# AT28C256_zif.net
KiCad netlist of a schematic drawn in EAGLE
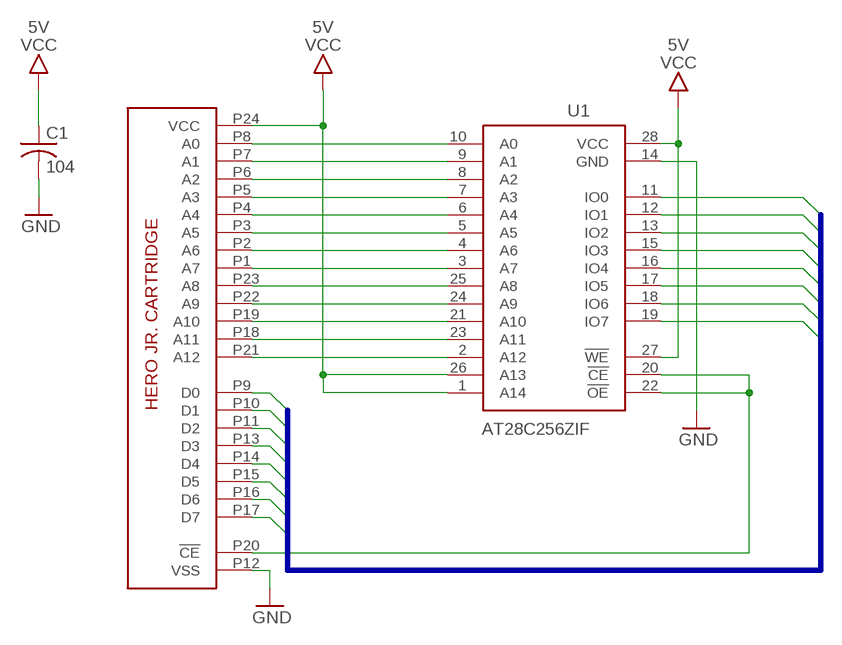
[diagram p0: schematic, sheet 1]

(export (version "E")
  (design (tool "Eeschema 10.0.6"))
  (components
    (comp (ref "C1")
      (value "104")
      (footprint "eagle-import:C050-025X075")
      (libsource (lib "eagle-import") (part "C-US050-025X075"))
    )
    (comp (ref "U$1")
      (value "HEROJRCART")
      (footprint "eagle-import:HEROJRCART")
      (libsource (lib "eagle-import") (part "HEROJRCART"))
    )
    (comp (ref "U1")
      (value "AT28C256ZIF")
      (footprint "eagle-import:DIL28-ZIF")
      (libsource (lib "eagle-import") (part "AT28C256ZIF"))
    )
  )
  (nets
    (net (code "1") (name "/D0") (class "Default")
      (node (ref "U$1") (pin "P9") (pinfunction "D0_P9") (pintype "bidirectional"))
      (node (ref "U1") (pin "11") (pinfunction "IO0_11") (pintype "bidirectional"))
    )
    (net (code "2") (name "/D1") (class "Default")
      (node (ref "U$1") (pin "P10") (pinfunction "D1_P10") (pintype "bidirectional"))
      (node (ref "U1") (pin "12") (pinfunction "IO1_12") (pintype "bidirectional"))
    )
    (net (code "3") (name "/D2") (class "Default")
      (node (ref "U$1") (pin "P11") (pinfunction "D2_P11") (pintype "bidirectional"))
      (node (ref "U1") (pin "13") (pinfunction "IO2_13") (pintype "bidirectional"))
    )
    (net (code "4") (name "/D3") (class "Default")
      (node (ref "U$1") (pin "P13") (pinfunction "D3_P13") (pintype "bidirectional"))
      (node (ref "U1") (pin "15") (pinfunction "IO3_15") (pintype "bidirectional"))
    )
    (net (code "5") (name "/D4") (class "Default")
      (node (ref "U$1") (pin "P14") (pinfunction "D4_P14") (pintype "bidirectional"))
      (node (ref "U1") (pin "16") (pinfunction "IO4_16") (pintype "bidirectional"))
    )
    (net (code "6") (name "/D5") (class "Default")
      (node (ref "U$1") (pin "P15") (pinfunction "D5_P15") (pintype "bidirectional"))
      (node (ref "U1") (pin "17") (pinfunction "IO5_17") (pintype "bidirectional"))
    )
    (net (code "7") (name "/D6") (class "Default")
      (node (ref "U$1") (pin "P16") (pinfunction "D6_P16") (pintype "bidirectional"))
      (node (ref "U1") (pin "18") (pinfunction "IO6_18") (pintype "bidirectional"))
    )
    (net (code "8") (name "/D7") (class "Default")
      (node (ref "U$1") (pin "P17") (pinfunction "D7_P17") (pintype "bidirectional"))
      (node (ref "U1") (pin "19") (pinfunction "IO7_19") (pintype "bidirectional"))
    )
    (net (code "9") (name "5V") (class "Default")
      (node (ref "C1") (pin "1") (pinfunction "1_1") (pintype "passive"))
      (node (ref "U$1") (pin "P24") (pinfunction "VCC_P24") (pintype "bidirectional"))
      (node (ref "U1") (pin "1") (pinfunction "A14_1") (pintype "bidirectional"))
      (node (ref "U1") (pin "26") (pinfunction "A13_26") (pintype "bidirectional"))
      (node (ref "U1") (pin "27") (pinfunction "~{WE}_27") (pintype "bidirectional"))
      (node (ref "U1") (pin "28") (pinfunction "VCC_28") (pintype "bidirectional"))
    )
    (net (code "10") (name "GND") (class "Default")
      (node (ref "C1") (pin "2") (pinfunction "2_2") (pintype "passive"))
      (node (ref "U$1") (pin "P12") (pinfunction "VSS_P12") (pintype "bidirectional"))
      (node (ref "U1") (pin "14") (pinfunction "GND_14") (pintype "bidirectional"))
    )
    (net (code "11") (name "Net-(U$1-A0)") (class "Default")
      (node (ref "U$1") (pin "P8") (pinfunction "A0_P8") (pintype "bidirectional"))
      (node (ref "U1") (pin "10") (pinfunction "A0_10") (pintype "bidirectional"))
    )
    (net (code "12") (name "Net-(U$1-A1)") (class "Default")
      (node (ref "U$1") (pin "P7") (pinfunction "A1_P7") (pintype "bidirectional"))
      (node (ref "U1") (pin "9") (pinfunction "A1_9") (pintype "bidirectional"))
    )
    (net (code "13") (name "Net-(U$1-A2)") (class "Default")
      (node (ref "U$1") (pin "P6") (pinfunction "A2_P6") (pintype "bidirectional"))
      (node (ref "U1") (pin "8") (pinfunction "A2_8") (pintype "bidirectional"))
    )
    (net (code "14") (name "Net-(U$1-A3)") (class "Default")
      (node (ref "U$1") (pin "P5") (pinfunction "A3_P5") (pintype "bidirectional"))
      (node (ref "U1") (pin "7") (pinfunction "A3_7") (pintype "bidirectional"))
    )
    (net (code "15") (name "Net-(U$1-A4)") (class "Default")
      (node (ref "U$1") (pin "P4") (pinfunction "A4_P4") (pintype "bidirectional"))
      (node (ref "U1") (pin "6") (pinfunction "A4_6") (pintype "bidirectional"))
    )
    (net (code "16") (name "Net-(U$1-A5)") (class "Default")
      (node (ref "U$1") (pin "P3") (pinfunction "A5_P3") (pintype "bidirectional"))
      (node (ref "U1") (pin "5") (pinfunction "A5_5") (pintype "bidirectional"))
    )
    (net (code "17") (name "Net-(U$1-A6)") (class "Default")
      (node (ref "U$1") (pin "P2") (pinfunction "A6_P2") (pintype "bidirectional"))
      (node (ref "U1") (pin "4") (pinfunction "A6_4") (pintype "bidirectional"))
    )
    (net (code "18") (name "Net-(U$1-A7)") (class "Default")
      (node (ref "U$1") (pin "P1") (pinfunction "A7_P1") (pintype "bidirectional"))
      (node (ref "U1") (pin "3") (pinfunction "A7_3") (pintype "bidirectional"))
    )
    (net (code "19") (name "Net-(U$1-A8)") (class "Default")
      (node (ref "U$1") (pin "P23") (pinfunction "A8_P23") (pintype "bidirectional"))
      (node (ref "U1") (pin "25") (pinfunction "A8_25") (pintype "bidirectional"))
    )
    (net (code "20") (name "Net-(U$1-A9)") (class "Default")
      (node (ref "U$1") (pin "P22") (pinfunction "A9_P22") (pintype "bidirectional"))
      (node (ref "U1") (pin "24") (pinfunction "A9_24") (pintype "bidirectional"))
    )
    (net (code "21") (name "Net-(U$1-A10)") (class "Default")
      (node (ref "U$1") (pin "P19") (pinfunction "A10_P19") (pintype "bidirectional"))
      (node (ref "U1") (pin "21") (pinfunction "A10_21") (pintype "bidirectional"))
    )
    (net (code "22") (name "Net-(U$1-A11)") (class "Default")
      (node (ref "U$1") (pin "P18") (pinfunction "A11_P18") (pintype "bidirectional"))
      (node (ref "U1") (pin "23") (pinfunction "A11_23") (pintype "bidirectional"))
    )
    (net (code "23") (name "Net-(U$1-A12)") (class "Default")
      (node (ref "U$1") (pin "P21") (pinfunction "A12_P21") (pintype "bidirectional"))
      (node (ref "U1") (pin "2") (pinfunction "A12_2") (pintype "bidirectional"))
    )
    (net (code "24") (name "Net-(U$1-~{CE})") (class "Default")
      (node (ref "U$1") (pin "P20") (pinfunction "~{CE}_P20") (pintype "bidirectional"))
      (node (ref "U1") (pin "20") (pinfunction "~{CE}_20") (pintype "bidirectional"))
      (node (ref "U1") (pin "22") (pinfunction "~{OE}_22") (pintype "bidirectional"))
    )
  )
)
